# USB_Debug.net
KiCad netlist of a schematic drawn in Altium Designer
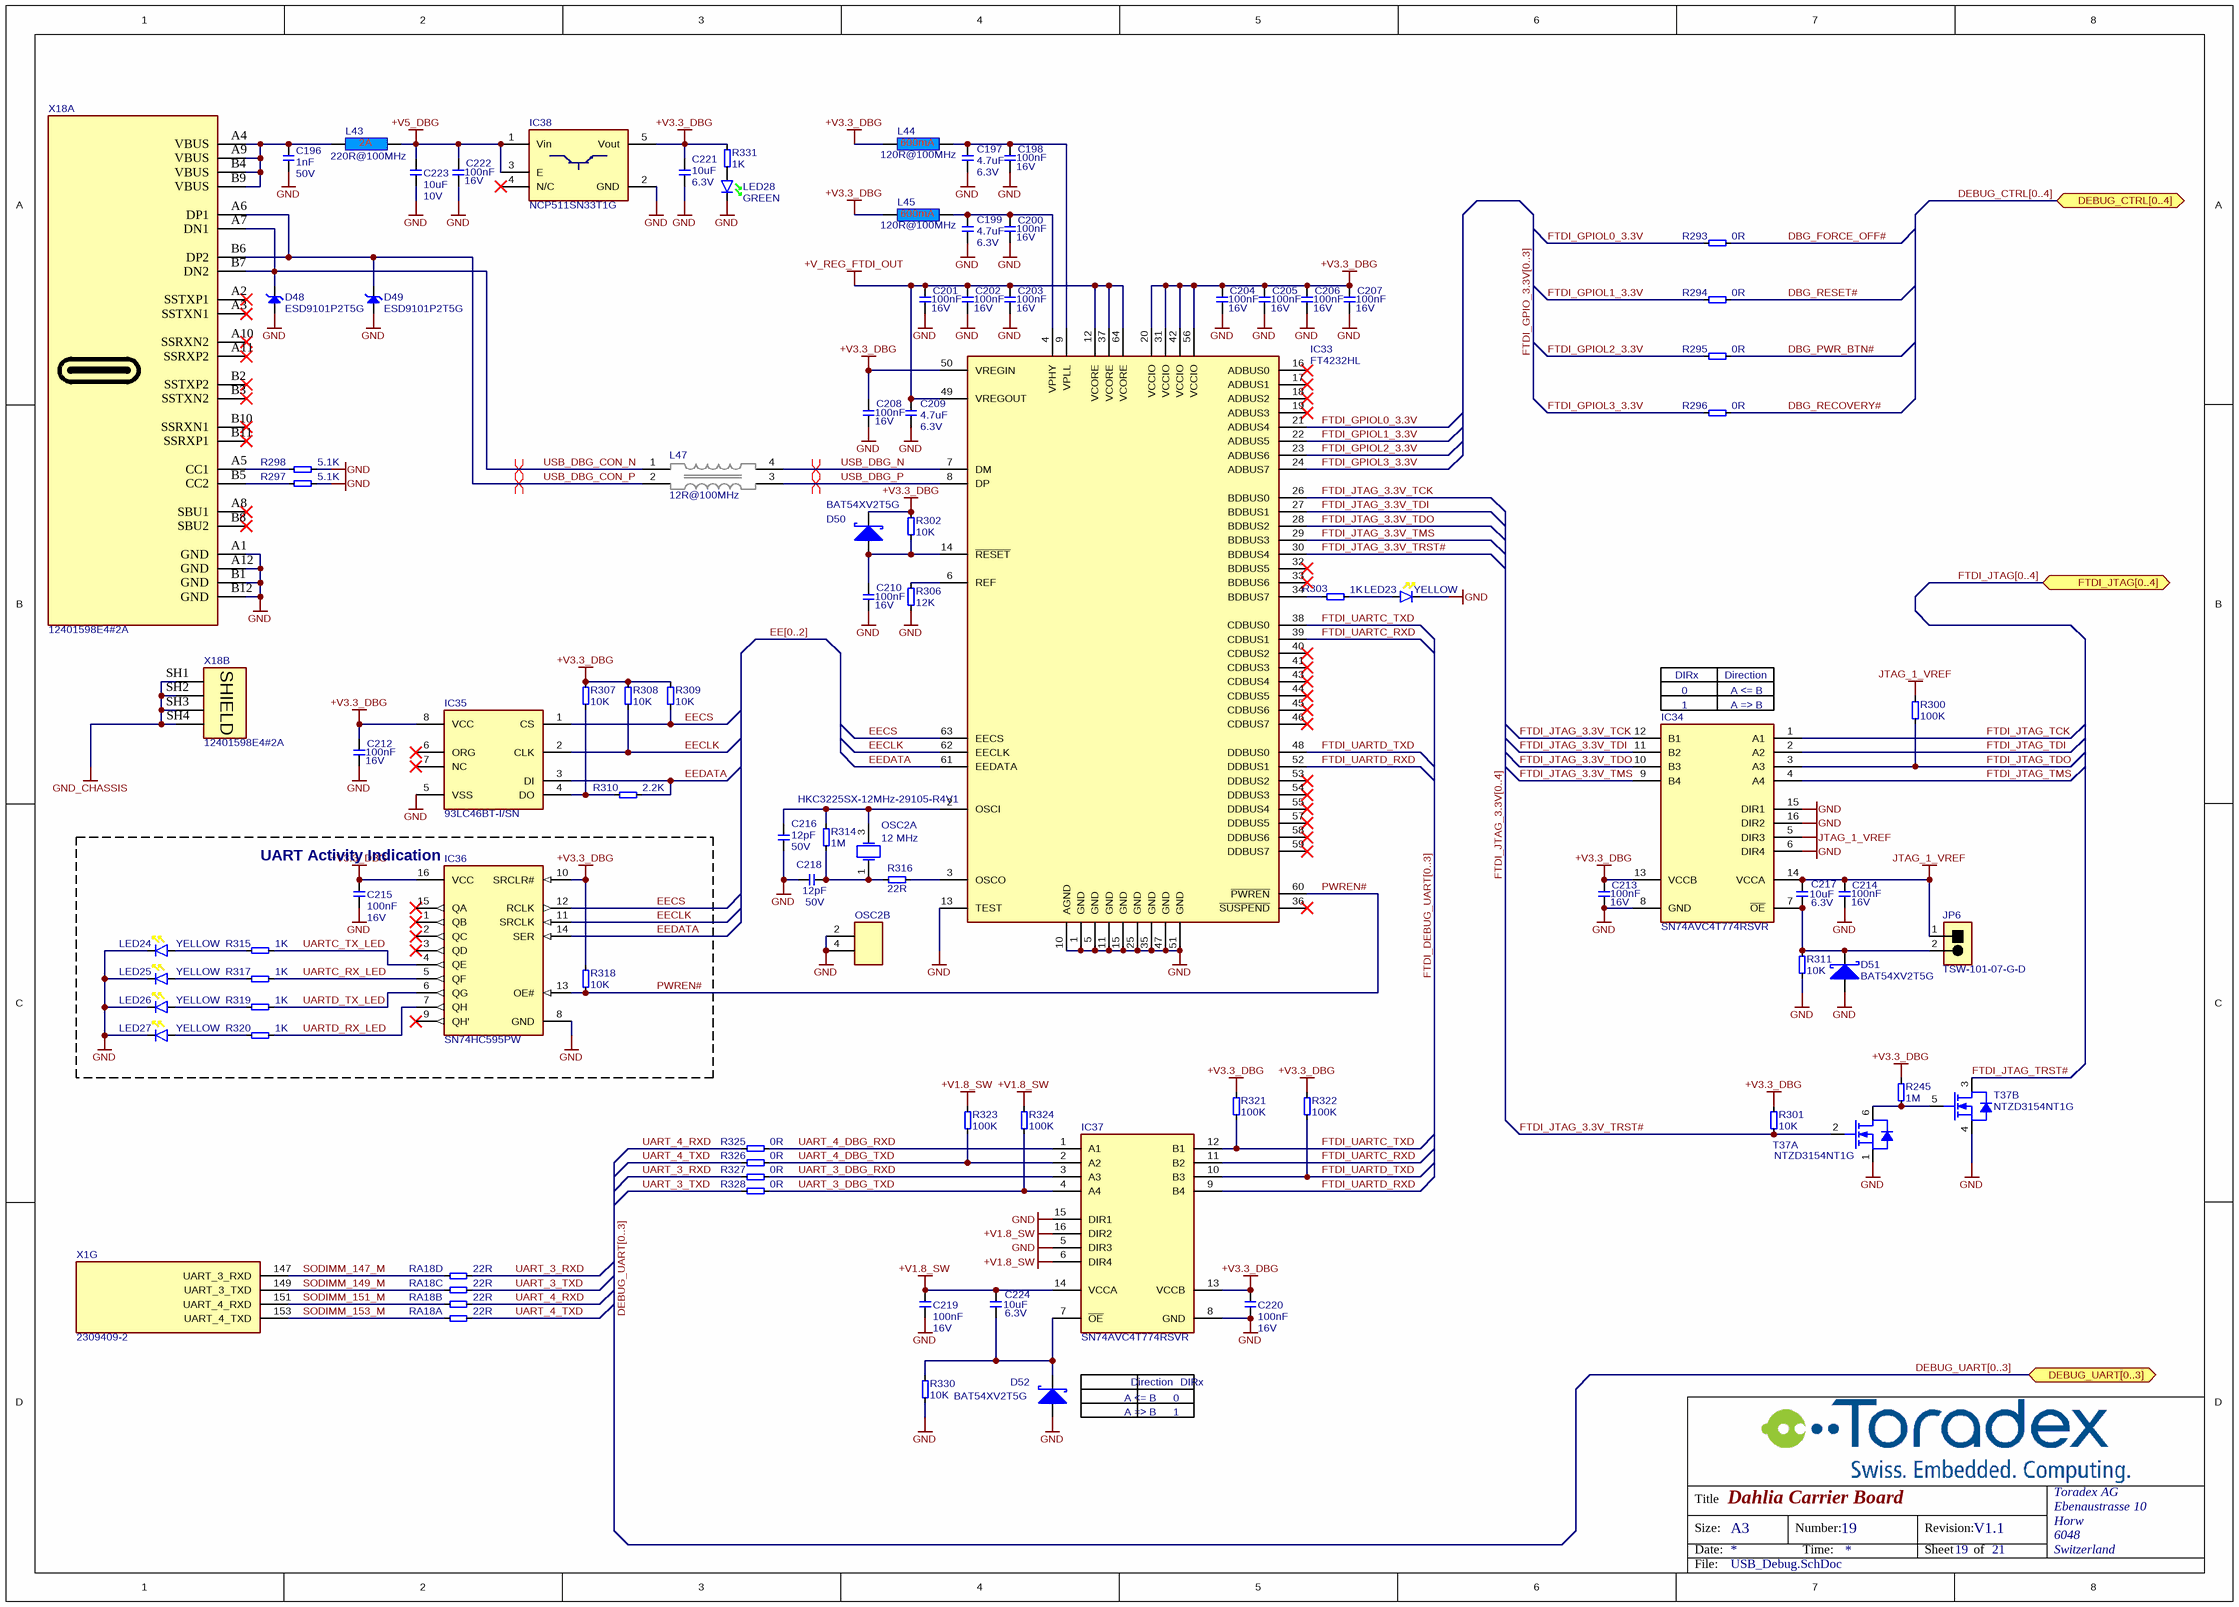
[diagram p0: USB_Debug.SchDoc]

(export (version "E")
  (design (tool "Eeschema 10.0.6"))
  (components
    (comp (ref "C196")
      (value "1nF")
      (footprint "CAPC1005X60N")
      (description "Capacitor Ceramic X7R 1nF 50V 10% 0402")
      (fields (field (name "TOLERANCE") "10%") (field (name "RATING") "50V"))
      (libsource (lib "Dahlia Carrier Board") (part "C-X7R-1nF-50V-10%-0402"))
    )
    (comp (ref "C197")
      (value "4.7uF")
      (footprint "CAPC1005X60N")
      (description "Capacitor Ceramic X5R 4.7uF 6.3V 20% 0402")
      (fields (field (name "TOLERANCE") "20%") (field (name "RATING") "6.3V"))
      (libsource (lib "Dahlia Carrier Board") (part "C-X5R-4.7u-6.3V-20%-0402"))
    )
    (comp (ref "C198")
      (value "100nF")
      (footprint "CAPC1005X60N")
      (description "Capacitor Ceramic X7R 100nF 16V 10% 0402")
      (fields (field (name "TOLERANCE") "10%") (field (name "RATING") "16V"))
      (libsource (lib "Dahlia Carrier Board") (part "C-X7R-100nF-16V-10%-0402"))
    )
    (comp (ref "C199")
      (value "4.7uF")
      (footprint "CAPC1005X60N")
      (description "Capacitor Ceramic X5R 4.7uF 6.3V 20% 0402")
      (fields (field (name "TOLERANCE") "20%") (field (name "RATING") "6.3V"))
      (libsource (lib "Dahlia Carrier Board") (part "C-X5R-4.7u-6.3V-20%-0402"))
    )
    (comp (ref "C200")
      (value "100nF")
      (footprint "CAPC1005X60N")
      (description "Capacitor Ceramic X7R 100nF 16V 10% 0402")
      (fields (field (name "TOLERANCE") "10%") (field (name "RATING") "16V"))
      (libsource (lib "Dahlia Carrier Board") (part "C-X7R-100nF-16V-10%-0402"))
    )
    (comp (ref "C201")
      (value "100nF")
      (footprint "CAPC1005X60N")
      (description "Capacitor Ceramic X7R 100nF 16V 10% 0402")
      (fields (field (name "TOLERANCE") "10%") (field (name "RATING") "16V"))
      (libsource (lib "Dahlia Carrier Board") (part "C-X7R-100nF-16V-10%-0402"))
    )
    (comp (ref "C202")
      (value "100nF")
      (footprint "CAPC1005X60N")
      (description "Capacitor Ceramic X7R 100nF 16V 10% 0402")
      (fields (field (name "TOLERANCE") "10%") (field (name "RATING") "16V"))
      (libsource (lib "Dahlia Carrier Board") (part "C-X7R-100nF-16V-10%-0402"))
    )
    (comp (ref "C203")
      (value "100nF")
      (footprint "CAPC1005X60N")
      (description "Capacitor Ceramic X7R 100nF 16V 10% 0402")
      (fields (field (name "TOLERANCE") "10%") (field (name "RATING") "16V"))
      (libsource (lib "Dahlia Carrier Board") (part "C-X7R-100nF-16V-10%-0402"))
    )
    (comp (ref "C204")
      (value "100nF")
      (footprint "CAPC1005X60N")
      (description "Capacitor Ceramic X7R 100nF 16V 10% 0402")
      (fields (field (name "TOLERANCE") "10%") (field (name "RATING") "16V"))
      (libsource (lib "Dahlia Carrier Board") (part "C-X7R-100nF-16V-10%-0402"))
    )
    (comp (ref "C205")
      (value "100nF")
      (footprint "CAPC1005X60N")
      (description "Capacitor Ceramic X7R 100nF 16V 10% 0402")
      (fields (field (name "TOLERANCE") "10%") (field (name "RATING") "16V"))
      (libsource (lib "Dahlia Carrier Board") (part "C-X7R-100nF-16V-10%-0402"))
    )
    (comp (ref "C206")
      (value "100nF")
      (footprint "CAPC1005X60N")
      (description "Capacitor Ceramic X7R 100nF 16V 10% 0402")
      (fields (field (name "TOLERANCE") "10%") (field (name "RATING") "16V"))
      (libsource (lib "Dahlia Carrier Board") (part "C-X7R-100nF-16V-10%-0402"))
    )
    (comp (ref "C207")
      (value "100nF")
      (footprint "CAPC1005X60N")
      (description "Capacitor Ceramic X7R 100nF 16V 10% 0402")
      (fields (field (name "TOLERANCE") "10%") (field (name "RATING") "16V"))
      (libsource (lib "Dahlia Carrier Board") (part "C-X7R-100nF-16V-10%-0402"))
    )
    (comp (ref "C208")
      (value "100nF")
      (footprint "CAPC1005X60N")
      (description "Capacitor Ceramic X7R 100nF 16V 10% 0402")
      (fields (field (name "TOLERANCE") "10%") (field (name "RATING") "16V"))
      (libsource (lib "Dahlia Carrier Board") (part "C-X7R-100nF-16V-10%-0402"))
    )
    (comp (ref "C209")
      (value "4.7uF")
      (footprint "CAPC1005X60N")
      (description "Capacitor Ceramic X5R 4.7uF 6.3V 20% 0402")
      (fields (field (name "TOLERANCE") "20%") (field (name "RATING") "6.3V"))
      (libsource (lib "Dahlia Carrier Board") (part "C-X5R-4.7u-6.3V-20%-0402"))
    )
    (comp (ref "C210")
      (value "100nF")
      (footprint "CAPC1005X60N")
      (description "Capacitor Ceramic X7R 100nF 16V 10% 0402")
      (fields (field (name "TOLERANCE") "10%") (field (name "RATING") "16V"))
      (libsource (lib "Dahlia Carrier Board") (part "C-X7R-100nF-16V-10%-0402"))
    )
    (comp (ref "C212")
      (value "100nF")
      (footprint "CAPC1005X60N")
      (description "Capacitor Ceramic X7R 100nF 16V 10% 0402")
      (fields (field (name "TOLERANCE") "10%") (field (name "RATING") "16V"))
      (libsource (lib "Dahlia Carrier Board") (part "C-X7R-100nF-16V-10%-0402"))
    )
    (comp (ref "C213")
      (value "100nF")
      (footprint "CAPC1005X60N")
      (description "Capacitor Ceramic X7R 100nF 16V 10% 0402")
      (fields (field (name "TOLERANCE") "10%") (field (name "RATING") "16V"))
      (libsource (lib "Dahlia Carrier Board") (part "C-X7R-100nF-16V-10%-0402"))
    )
    (comp (ref "C214")
      (value "100nF")
      (footprint "CAPC1005X60N")
      (description "Capacitor Ceramic X7R 100nF 16V 10% 0402")
      (fields (field (name "TOLERANCE") "10%") (field (name "RATING") "16V"))
      (libsource (lib "Dahlia Carrier Board") (part "C-X7R-100nF-16V-10%-0402"))
    )
    (comp (ref "C215")
      (value "100nF")
      (footprint "CAPC1005X60N")
      (description "Capacitor Ceramic X7R 100nF 16V 10% 0402")
      (fields (field (name "TOLERANCE") "10%") (field (name "RATING") "16V"))
      (libsource (lib "Dahlia Carrier Board") (part "C-X7R-100nF-16V-10%-0402"))
    )
    (comp (ref "C216")
      (value "12pF")
      (footprint "CAPC1005X60N")
      (description "Capacitor Ceramic NP0  12pF 50V 5% 0402")
      (fields (field (name "TOLERANCE") "5%") (field (name "RATING") "50V"))
      (libsource (lib "Dahlia Carrier Board") (part "C-NP0-12p-50V-5%-0402"))
    )
    (comp (ref "C217")
      (value "10uF")
      (footprint "CAPC1005X60N")
      (description "Capacitor Ceramic X5R 10uF 6.3V 20% 0402")
      (fields (field (name "TOLERANCE") "20%") (field (name "RATING") "6.3V"))
      (libsource (lib "Dahlia Carrier Board") (part "C-X5R-10u-6.3V-20%-0402"))
    )
    (comp (ref "C218")
      (value "12pF")
      (footprint "CAPC1005X60N")
      (description "Capacitor Ceramic NP0  12pF 50V 5% 0402")
      (fields (field (name "TOLERANCE") "5%") (field (name "RATING") "50V"))
      (libsource (lib "Dahlia Carrier Board") (part "C-NP0-12p-50V-5%-0402"))
    )
    (comp (ref "C219")
      (value "100nF")
      (footprint "CAPC1005X60N")
      (description "Capacitor Ceramic X7R 100nF 16V 10% 0402")
      (fields (field (name "TOLERANCE") "10%") (field (name "RATING") "16V"))
      (libsource (lib "Dahlia Carrier Board") (part "C-X7R-100nF-16V-10%-0402"))
    )
    (comp (ref "C220")
      (value "100nF")
      (footprint "CAPC1005X60N")
      (description "Capacitor Ceramic X7R 100nF 16V 10% 0402")
      (fields (field (name "TOLERANCE") "10%") (field (name "RATING") "16V"))
      (libsource (lib "Dahlia Carrier Board") (part "C-X7R-100nF-16V-10%-0402"))
    )
    (comp (ref "C221")
      (value "10uF")
      (footprint "CAPC1005X60N")
      (description "Capacitor Ceramic X5R 10uF 6.3V 20% 0402")
      (fields (field (name "TOLERANCE") "20%") (field (name "RATING") "6.3V"))
      (libsource (lib "Dahlia Carrier Board") (part "C-X5R-10u-6.3V-20%-0402"))
    )
    (comp (ref "C222")
      (value "100nF")
      (footprint "CAPC1005X60N")
      (description "Capacitor Ceramic X7R 100nF 16V 10% 0402")
      (fields (field (name "TOLERANCE") "10%") (field (name "RATING") "16V"))
      (libsource (lib "Dahlia Carrier Board") (part "C-X7R-100nF-16V-10%-0402"))
    )
    (comp (ref "C223")
      (value "10uF")
      (footprint "T_CAPC0603X33N")
      (description "Capacitor Ceramic X5R 10uF 10V 20% 0603")
      (fields (field (name "TOLERANCE") "20%") (field (name "RATING") "10V"))
      (libsource (lib "Dahlia Carrier Board") (part "C-X5R-10uF-10V-20%-0603"))
    )
    (comp (ref "C224")
      (value "10uF")
      (footprint "CAPC1005X60N")
      (description "Capacitor Ceramic X5R 10uF 6.3V 20% 0402")
      (fields (field (name "TOLERANCE") "20%") (field (name "RATING") "6.3V"))
      (libsource (lib "Dahlia Carrier Board") (part "C-X5R-10u-6.3V-20%-0402"))
    )
    (comp (ref "D48")
      (value "ESD9101P2T5G")
      (footprint "SOD-923")
      (description "ESD Protection Diode")
      (fields (field (name "MANUFACTURER PART NO.") "ESD9101P2T5G"))
      (libsource (lib "Dahlia Carrier Board") (part "D-OnSemi-ESD9101P2T5G"))
    )
    (comp (ref "D49")
      (value "ESD9101P2T5G")
      (footprint "SOD-923")
      (description "ESD Protection Diode")
      (fields (field (name "MANUFACTURER PART NO.") "ESD9101P2T5G"))
      (libsource (lib "Dahlia Carrier Board") (part "D-OnSemi-ESD9101P2T5G"))
    )
    (comp (ref "D50")
      (value "BAT54XV2T5G")
      (footprint "SOD-523")
      (description "Schottky Barrier Rectifier")
      (fields (field (name "MANUFACTURER PART NO.") "BAT54XV2T5G"))
      (libsource (lib "Dahlia Carrier Board") (part "D-BAT54-SOD523"))
    )
    (comp (ref "D51")
      (value "BAT54XV2T5G")
      (footprint "SOD-523")
      (description "Schottky Barrier Rectifier")
      (fields (field (name "MANUFACTURER PART NO.") "BAT54XV2T5G"))
      (libsource (lib "Dahlia Carrier Board") (part "D-BAT54-SOD523"))
    )
    (comp (ref "D52")
      (value "BAT54XV2T5G")
      (footprint "SOD-523")
      (description "Schottky Barrier Rectifier")
      (fields (field (name "MANUFACTURER PART NO.") "BAT54XV2T5G"))
      (libsource (lib "Dahlia Carrier Board") (part "D-BAT54-SOD523"))
    )
    (comp (ref "IC33")
      (value "FT4232HL")
      (footprint "LQFP-64")
      (description "Quad High Speed USB to Multipurpose UART/MPSSE")
      (fields (field (name "MANUFACTURER PART NO.") "FT4232HL"))
      (libsource (lib "Dahlia Carrier Board") (part "IC-FTDI-FT4232HL"))
    )
    (comp (ref "IC34")
      (value "SN74AVC4T774RSVR")
      (footprint "IC-UQFN40P180X210X55-16N")
      (description "4 Bit Bidirectional l Voltage Level Translator, Configurable Direction, UFQFN-16 package")
      (fields (field (name "MANUFACTURER PART NO.") "SN74AVC4T774RSVR"))
      (libsource (lib "") (part "IC-TI-SN74AVC4T774RSVR_1"))
    )
    (comp (ref "IC35")
      (value "93LC46BT")
      (footprint "SOIC127P600X173-8N")
      (description "EEPROM, 1k, 64x16, serial, SOIC8")
      (fields (field (name "MANUFACTURER PART NO.") "93LC46BT-I/SN"))
      (libsource (lib "Dahlia Carrier Board") (part "IC-MC-93LC46BT-I/SN"))
    )
    (comp (ref "IC36")
      (value "SN74HC595PW")
      (footprint "IC_TSOP65P640X120-16N")
      (description "8-Bit Shift Registers With 3-State Output Registers")
      (fields (field (name "MANUFACTURER PART NO.") "SN74HC595PW"))
      (libsource (lib "Dahlia Carrier Board") (part "IC-TI-SN74HC595PW"))
    )
    (comp (ref "IC37")
      (value "SN74AVC4T774RSVR")
      (footprint "IC-UQFN40P180X210X55-16N")
      (description "4 Bit Bidirectional l Voltage Level Translator, Configurable Direction, UFQFN-16 package")
      (fields (field (name "MANUFACTURER PART NO.") "SN74AVC4T774RSVR"))
      (libsource (lib "Dahlia Carrier Board") (part "IC-TI-SN74AVC4T774RSVR"))
    )
    (comp (ref "IC38")
      (value "NCP511SN33T1G")
      (footprint "SOT95P279X142-5N")
      (description "NCP511SN33T1G LDO Regulator")
      (fields (field (name "MANUFACTURER PART NO.") "NCP511SN33T1G"))
      (libsource (lib "Dahlia Carrier Board") (part "IC-ON-NCP511SN33T1G"))
    )
    (comp (ref "JP6")
      (value "TSW-101-07-G-D")
      (footprint "T_Samtec_TSW-101-07-G-D")
      (description "Header male, 1x2 Pins, 2.54 mm pitch")
      (libsource (lib "Dahlia Carrier Board") (part "CON-Samtec-TSW-101-07-G-D"))
    )
    (comp (ref "L43")
      (value "220R@100MHz")
      (footprint "INDC1608X95N")
      (description "220R@100MHz 2A EMI FILTER")
      (fields (field (name "TOLERANCE") "25%"))
      (libsource (lib "Dahlia Carrier Board") (part "L-220R@100MHz-2A-25%-0603"))
    )
    (comp (ref "L44")
      (value "120R@100MHz")
      (footprint "INDC1005X60N")
      (description "120R@100MHz 600mA EMI FILTER")
      (fields (field (name "TOLERANCE") "25%"))
      (libsource (lib "Dahlia Carrier Board") (part "Lemv-120R-600mA-25%-0402"))
    )
    (comp (ref "L45")
      (value "120R@100MHz")
      (footprint "INDC1005X60N")
      (description "120R@100MHz 600mA EMI FILTER")
      (fields (field (name "TOLERANCE") "25%"))
      (libsource (lib "Dahlia Carrier Board") (part "Lemv-120R-600mA-25%-0402"))
    )
    (comp (ref "L47")
      (value "12R@100MHz")
      (footprint "T_Panasonic_EXC14CH120U")
      (description "Common Mode Choke High Speed 12R 100mA")
      (fields (field (name "TOLERANCE") "25%") (field (name "MANUFACTURER PART NO.") "EXC14CH120U"))
      (libsource (lib "Dahlia Carrier Board") (part "L-Panasonic-EXC14CH120U-12R@100MHz-1000mA-25%"))
    )
    (comp (ref "LED23")
      (value "LTST-C190KSKT")
      (footprint "T_Liteon_LTST-C190KSKT")
      (description "LED yellow Lite-On LTST-C190KSKT")
      (fields (field (name "COLOR") "YELLOW"))
      (libsource (lib "Dahlia Carrier Board") (part "LED-LiteOn-LTST-C190KSKT"))
    )
    (comp (ref "LED24")
      (value "LTST-C190KSKT")
      (footprint "T_Liteon_LTST-C190KSKT")
      (description "LED yellow Lite-On LTST-C190KSKT")
      (fields (field (name "COLOR") "YELLOW"))
      (libsource (lib "Dahlia Carrier Board") (part "LED-LiteOn-LTST-C190KSKT"))
    )
    (comp (ref "LED25")
      (value "LTST-C190KSKT")
      (footprint "T_Liteon_LTST-C190KSKT")
      (description "LED yellow Lite-On LTST-C190KSKT")
      (fields (field (name "COLOR") "YELLOW"))
      (libsource (lib "Dahlia Carrier Board") (part "LED-LiteOn-LTST-C190KSKT"))
    )
    (comp (ref "LED26")
      (value "LTST-C190KSKT")
      (footprint "T_Liteon_LTST-C190KSKT")
      (description "LED yellow Lite-On LTST-C190KSKT")
      (fields (field (name "COLOR") "YELLOW"))
      (libsource (lib "Dahlia Carrier Board") (part "LED-LiteOn-LTST-C190KSKT"))
    )
    (comp (ref "LED27")
      (value "LTST-C190KSKT")
      (footprint "T_Liteon_LTST-C190KSKT")
      (description "LED yellow Lite-On LTST-C190KSKT")
      (fields (field (name "COLOR") "YELLOW"))
      (libsource (lib "Dahlia Carrier Board") (part "LED-LiteOn-LTST-C190KSKT"))
    )
    (comp (ref "LED28")
      (value "LTST-C190GKT")
      (footprint "T_Liteon_LTST-C190GKT")
      (description "LED green Lite-ON LTST-C190GKT")
      (fields (field (name "COLOR") "GREEN"))
      (libsource (lib "Dahlia Carrier Board") (part "LED-LiteOn-LTST-C190GKT"))
    )
    (comp (ref "OSC2")
      (value "HKC3225SX-12MHz-29105-R4V1")
      (footprint "OSC-SMD-3.2mmx2.5mm")
      (fields (field (name "TOLERANCE") "+/- 30 ppm") (field (name "ALTIUM_VALUE") "12 MHz"))
      (libsource (lib "Dahlia Carrier Board") (part "OSC-HKC-HKC3225SX-12MHz-29105-R4V1"))
    )
    (comp (ref "R245")
      (value "1M")
      (footprint "RESC1005X40N")
      (description "Resistor 1 Mohm 63mW 5% 0402")
      (fields (field (name "TOLERANCE") "5%"))
      (libsource (lib "Dahlia Carrier Board") (part "R-1M-63mW-5%-0402"))
    )
    (comp (ref "R293")
      (value "0R")
      (footprint "T_RESC0603X30N")
      (description "Resistor 0 ohm 63mW 1% 0603")
      (fields (field (name "TOLERANCE") "1%"))
      (libsource (lib "Dahlia Carrier Board") (part "R-0R-63mW-1%-0603"))
    )
    (comp (ref "R294")
      (value "0R")
      (footprint "T_RESC0603X30N")
      (description "Resistor 0 ohm 63mW 1% 0603")
      (fields (field (name "TOLERANCE") "1%"))
      (libsource (lib "Dahlia Carrier Board") (part "R-0R-63mW-1%-0603"))
    )
    (comp (ref "R295")
      (value "0R")
      (footprint "T_RESC0603X30N")
      (description "Resistor 0 ohm 63mW 1% 0603")
      (fields (field (name "TOLERANCE") "1%"))
      (libsource (lib "Dahlia Carrier Board") (part "R-0R-63mW-1%-0603"))
    )
    (comp (ref "R296")
      (value "0R")
      (footprint "T_RESC0603X30N")
      (description "Resistor 0 ohm 63mW 1% 0603")
      (fields (field (name "TOLERANCE") "1%"))
      (libsource (lib "Dahlia Carrier Board") (part "R-0R-63mW-1%-0603"))
    )
    (comp (ref "R297")
      (value "5.1K")
      (footprint "T_RESC0603X30N")
      (description "Resistor 5.1 Kohm 63mW 1% 0603")
      (fields (field (name "TOLERANCE") "1%"))
      (libsource (lib "Dahlia Carrier Board") (part "R-5.1K-63mW-1%-0603"))
    )
    (comp (ref "R298")
      (value "5.1K")
      (footprint "T_RESC0603X30N")
      (description "Resistor 5.1 Kohm 63mW 1% 0603")
      (fields (field (name "TOLERANCE") "1%"))
      (libsource (lib "Dahlia Carrier Board") (part "R-5.1K-63mW-1%-0603"))
    )
    (comp (ref "R300")
      (value "100K")
      (footprint "RESC1005X40N")
      (description "Resistor 100 Kohm 63mW 5% 0402")
      (fields (field (name "TOLERANCE") "5%"))
      (libsource (lib "Dahlia Carrier Board") (part "R-100K-63mW-5%-0402"))
    )
    (comp (ref "R301")
      (value "10K")
      (footprint "RESC1005X40N")
      (description "Resistor 10 Kohm 63mW 5% 0402")
      (fields (field (name "TOLERANCE") "5%"))
      (libsource (lib "Dahlia Carrier Board") (part "R-10K-63mW-5%-0402"))
    )
    (comp (ref "R302")
      (value "10K")
      (footprint "RESC1005X40N")
      (description "Resistor 10 Kohm 63mW 5% 0402")
      (fields (field (name "TOLERANCE") "5%"))
      (libsource (lib "Dahlia Carrier Board") (part "R-10K-63mW-5%-0402"))
    )
    (comp (ref "R303")
      (value "1K")
      (footprint "RESC1005X40N")
      (description "Resistor 1 Kohm 63mW 5% 0402")
      (fields (field (name "TOLERANCE") "5%"))
      (libsource (lib "Dahlia Carrier Board") (part "R-1K-63mW-5%-0402"))
    )
    (comp (ref "R306")
      (value "12K")
      (footprint "RESC1005X40N")
      (description "Resistor 12 Kohm 63mW 1% 0402")
      (fields (field (name "TOLERANCE") "1%"))
      (libsource (lib "Dahlia Carrier Board") (part "R-12K-63mW-1%-0402"))
    )
    (comp (ref "R307")
      (value "10K")
      (footprint "RESC1005X40N")
      (description "Resistor 10 Kohm 63mW 5% 0402")
      (fields (field (name "TOLERANCE") "5%"))
      (libsource (lib "Dahlia Carrier Board") (part "R-10K-63mW-5%-0402"))
    )
    (comp (ref "R308")
      (value "10K")
      (footprint "RESC1005X40N")
      (description "Resistor 10 Kohm 63mW 5% 0402")
      (fields (field (name "TOLERANCE") "5%"))
      (libsource (lib "Dahlia Carrier Board") (part "R-10K-63mW-5%-0402"))
    )
    (comp (ref "R309")
      (value "10K")
      (footprint "RESC1005X40N")
      (description "Resistor 10 Kohm 63mW 5% 0402")
      (fields (field (name "TOLERANCE") "5%"))
      (libsource (lib "Dahlia Carrier Board") (part "R-10K-63mW-5%-0402"))
    )
    (comp (ref "R310")
      (value "2.2K")
      (footprint "RESC1005X40N")
      (description "Resistor 2.2 Kohm 63mW 5% 0402")
      (fields (field (name "TOLERANCE") "5%"))
      (libsource (lib "Dahlia Carrier Board") (part "R-2.2K-63mW-5%-0402"))
    )
    (comp (ref "R311")
      (value "10K")
      (footprint "RESC1005X40N")
      (description "Resistor 10 Kohm 63mW 5% 0402")
      (fields (field (name "TOLERANCE") "5%"))
      (libsource (lib "Dahlia Carrier Board") (part "R-10K-63mW-5%-0402"))
    )
    (comp (ref "R314")
      (value "1M")
      (footprint "T_RESC0603X30N")
      (description "Resistor 1Mohm 63mW 5% 0603")
      (fields (field (name "TOLERANCE") "5%") (field (name "Comment") "1MR"))
      (libsource (lib "Dahlia Carrier Board") (part "R-1M-63mW-5%-0603"))
    )
    (comp (ref "R315")
      (value "1K")
      (footprint "RESC1005X40N")
      (description "Resistor 1 Kohm 63mW 5% 0402")
      (fields (field (name "TOLERANCE") "5%"))
      (libsource (lib "Dahlia Carrier Board") (part "R-1K-63mW-5%-0402"))
    )
    (comp (ref "R316")
      (value "22R")
      (footprint "RESC1005X40N")
      (description "Resistor 22 ohm 63mW 5% 0402")
      (fields (field (name "TOLERANCE") "5%"))
      (libsource (lib "Dahlia Carrier Board") (part "R-22R-63mW-5%-0402"))
    )
    (comp (ref "R317")
      (value "1K")
      (footprint "RESC1005X40N")
      (description "Resistor 1 Kohm 63mW 5% 0402")
      (fields (field (name "TOLERANCE") "5%"))
      (libsource (lib "Dahlia Carrier Board") (part "R-1K-63mW-5%-0402"))
    )
    (comp (ref "R318")
      (value "10K")
      (footprint "RESC1005X40N")
      (description "Resistor 10 Kohm 63mW 5% 0402")
      (fields (field (name "TOLERANCE") "5%"))
      (libsource (lib "Dahlia Carrier Board") (part "R-10K-63mW-5%-0402"))
    )
    (comp (ref "R319")
      (value "1K")
      (footprint "RESC1005X40N")
      (description "Resistor 1 Kohm 63mW 5% 0402")
      (fields (field (name "TOLERANCE") "5%"))
      (libsource (lib "Dahlia Carrier Board") (part "R-1K-63mW-5%-0402"))
    )
    (comp (ref "R320")
      (value "1K")
      (footprint "RESC1005X40N")
      (description "Resistor 1 Kohm 63mW 5% 0402")
      (fields (field (name "TOLERANCE") "5%"))
      (libsource (lib "Dahlia Carrier Board") (part "R-1K-63mW-5%-0402"))
    )
    (comp (ref "R321")
      (value "100K")
      (footprint "RESC1005X40N")
      (description "Resistor 100 Kohm 63mW 5% 0402")
      (fields (field (name "TOLERANCE") "5%"))
      (libsource (lib "Dahlia Carrier Board") (part "R-100K-63mW-5%-0402"))
    )
    (comp (ref "R322")
      (value "100K")
      (footprint "RESC1005X40N")
      (description "Resistor 100 Kohm 63mW 5% 0402")
      (fields (field (name "TOLERANCE") "5%"))
      (libsource (lib "Dahlia Carrier Board") (part "R-100K-63mW-5%-0402"))
    )
    (comp (ref "R323")
      (value "100K")
      (footprint "RESC1005X40N")
      (description "Resistor 100 Kohm 63mW 5% 0402")
      (fields (field (name "TOLERANCE") "5%"))
      (libsource (lib "Dahlia Carrier Board") (part "R-100K-63mW-5%-0402"))
    )
    (comp (ref "R324")
      (value "100K")
      (footprint "RESC1005X40N")
      (description "Resistor 100 Kohm 63mW 5% 0402")
      (fields (field (name "TOLERANCE") "5%"))
      (libsource (lib "Dahlia Carrier Board") (part "R-100K-63mW-5%-0402"))
    )
    (comp (ref "R325")
      (value "0R")
      (footprint "T_RESC0603X30N")
      (description "Resistor 0 ohm 63mW 1% 0603")
      (fields (field (name "TOLERANCE") "1%"))
      (libsource (lib "Dahlia Carrier Board") (part "R-0R-63mW-1%-0603"))
    )
    (comp (ref "R326")
      (value "0R")
      (footprint "T_RESC0603X30N")
      (description "Resistor 0 ohm 63mW 1% 0603")
      (fields (field (name "TOLERANCE") "1%"))
      (libsource (lib "Dahlia Carrier Board") (part "R-0R-63mW-1%-0603"))
    )
    (comp (ref "R327")
      (value "0R")
      (footprint "T_RESC0603X30N")
      (description "Resistor 0 ohm 63mW 1% 0603")
      (fields (field (name "TOLERANCE") "1%"))
      (libsource (lib "Dahlia Carrier Board") (part "R-0R-63mW-1%-0603"))
    )
    (comp (ref "R328")
      (value "0R")
      (footprint "T_RESC0603X30N")
      (description "Resistor 0 ohm 63mW 1% 0603")
      (fields (field (name "TOLERANCE") "1%"))
      (libsource (lib "Dahlia Carrier Board") (part "R-0R-63mW-1%-0603"))
    )
    (comp (ref "R330")
      (value "10K")
      (footprint "RESC1005X40N")
      (description "Resistor 10 Kohm 63mW 5% 0402")
      (fields (field (name "TOLERANCE") "5%"))
      (libsource (lib "Dahlia Carrier Board") (part "R-10K-63mW-5%-0402"))
    )
    (comp (ref "R331")
      (value "1K")
      (footprint "RESC1005X40N")
      (description "Resistor 1 Kohm 63mW 5% 0402")
      (fields (field (name "TOLERANCE") "5%"))
      (libsource (lib "Dahlia Carrier Board") (part "R-1K-63mW-5%-0402"))
    )
    (comp (ref "RA18")
      (value "22R")
      (footprint "T_Resistor_Array_X4")
      (description "Resistor Array 22 R 63mW 5% 1206")
      (fields (field (name "TOLERANCE") "5%"))
      (libsource (lib "Dahlia Carrier Board") (part "RA-22R-63mW-5%-1206-div"))
    )
    (comp (ref "T37")
      (value "T-ONSemi-NTZD3154NT1G")
      (footprint "SOTFL50P160X60-6N")
      (description "Dual N-Channel 20V (D-S)  MOSFET")
      (fields (field (name "MANUFACTURER PART NO.") "NTZD3154NT1G"))
      (libsource (lib "Dahlia Carrier Board") (part "T-ONSemi-NTZD3154NT1G"))
    )
    (comp (ref "X1")
      (value "2309409-2")
      (footprint "CON-TE-2309409-2-SOLDERABLE-STANDOFFS")
      (description "DDR4 SODIMM Socket, 260 pins, 5.2mm(H), 0.5mm Pitch")
      (libsource (lib "Dahlia Carrier Board") (part "CON-TE-2309409-2"))
    )
    (comp (ref "X18")
      (value "12401598E4#2A")
      (footprint "CON-AMPHENOL-12401598E4#2A")
      (description "USB 3.1 Gen 2, Input Output Connectors, USB type C, Receptacle, Top mount, dual-row SMT, 1.6mmPCB")
      (fields (field (name "MANUFACTURER PART NO.") "12401598E4#2A"))
      (libsource (lib "Dahlia Carrier Board") (part "CON-Amphenol-12401598E4#2A"))
    )
  )
  (nets
    (net (code "31") (name "+V1.8_SW") (class "Default")
      (node (ref "C219") (pin "2") (pinfunction "2_2") (pintype "passive"))
      (node (ref "C224") (pin "2") (pinfunction "2_2") (pintype "passive"))
      (node (ref "IC37") (pin "14") (pinfunction "VCCA_14") (pintype "power_in"))
      (node (ref "IC37") (pin "16") (pinfunction "DIR2_16") (pintype "passive"))
      (node (ref "IC37") (pin "6") (pinfunction "DIR4_6") (pintype "passive"))
      (node (ref "R323") (pin "1") (pinfunction "1_1") (pintype "passive"))
      (node (ref "R324") (pin "2") (pinfunction "2_2") (pintype "passive"))
    )
    (net (code "32") (name "+V3.3_DBG") (class "Default")
      (node (ref "C204") (pin "2") (pinfunction "2_2") (pintype "passive"))
      (node (ref "C205") (pin "2") (pinfunction "2_2") (pintype "passive"))
      (node (ref "C206") (pin "2") (pinfunction "2_2") (pintype "passive"))
      (node (ref "C207") (pin "2") (pinfunction "2_2") (pintype "passive"))
      (node (ref "C208") (pin "2") (pinfunction "2_2") (pintype "passive"))
      (node (ref "C212") (pin "2") (pinfunction "2_2") (pintype "passive"))
      (node (ref "C213") (pin "2") (pinfunction "2_2") (pintype "passive"))
      (node (ref "C215") (pin "2") (pinfunction "2_2") (pintype "passive"))
      (node (ref "C220") (pin "2") (pinfunction "2_2") (pintype "passive"))
      (node (ref "C221") (pin "2") (pinfunction "2_2") (pintype "passive"))
      (node (ref "D50") (pin "C") (pinfunction "C_C") (pintype "passive"))
      (node (ref "IC33") (pin "20") (pinfunction "VCCIO_20") (pintype "passive"))
      (node (ref "IC33") (pin "31") (pinfunction "VCCIO_31") (pintype "passive"))
      (node (ref "IC33") (pin "42") (pinfunction "VCCIO_42") (pintype "passive"))
      (node (ref "IC33") (pin "50") (pinfunction "VREGIN_50") (pintype "passive"))
      (node (ref "IC33") (pin "56") (pinfunction "VCCIO_56") (pintype "passive"))
      (node (ref "IC34") (pin "13") (pinfunction "VCCB_13") (pintype "power_in"))
      (node (ref "IC35") (pin "8") (pinfunction "VCC_8") (pintype "passive"))
      (node (ref "IC36") (pin "10") (pinfunction "SRCLR#_10") (pintype "input"))
      (node (ref "IC36") (pin "16") (pinfunction "VCC_16") (pintype "power_in"))
      (node (ref "IC37") (pin "13") (pinfunction "VCCB_13") (pintype "power_in"))
      (node (ref "IC38") (pin "5") (pinfunction "Vout_5") (pintype "passive"))
      (node (ref "L44") (pin "1") (pinfunction "1_1") (pintype "passive"))
      (node (ref "L45") (pin "1") (pinfunction "1_1") (pintype "passive"))
      (node (ref "R245") (pin "2") (pinfunction "2_2") (pintype "passive"))
      (node (ref "R301") (pin "2") (pinfunction "2_2") (pintype "passive"))
      (node (ref "R302") (pin "2") (pinfunction "2_2") (pintype "passive"))
      (node (ref "R307") (pin "2") (pinfunction "2_2") (pintype "passive"))
      (node (ref "R308") (pin "2") (pinfunction "2_2") (pintype "passive"))
      (node (ref "R309") (pin "2") (pinfunction "2_2") (pintype "passive"))
      (node (ref "R318") (pin "2") (pinfunction "2_2") (pintype "passive"))
      (node (ref "R321") (pin "1") (pinfunction "1_1") (pintype "passive"))
      (node (ref "R322") (pin "2") (pinfunction "2_2") (pintype "passive"))
      (node (ref "R331") (pin "2") (pinfunction "2_2") (pintype "passive"))
    )
    (net (code "33") (name "+V5_DBG") (class "Default")
      (node (ref "C222") (pin "2") (pinfunction "2_2") (pintype "passive"))
      (node (ref "C223") (pin "2") (pinfunction "2_2") (pintype "passive"))
      (node (ref "IC38") (pin "1") (pinfunction "Vin_1") (pintype "passive"))
      (node (ref "IC38") (pin "3") (pinfunction "E_3") (pintype "passive"))
      (node (ref "L43") (pin "1") (pinfunction "1_1") (pintype "passive"))
    )
    (net (code "34") (name "+V_REG_FTDI_OUT") (class "Default")
      (node (ref "C201") (pin "2") (pinfunction "2_2") (pintype "passive"))
      (node (ref "C202") (pin "2") (pinfunction "2_2") (pintype "passive"))
      (node (ref "C203") (pin "2") (pinfunction "2_2") (pintype "passive"))
      (node (ref "C209") (pin "2") (pinfunction "2_2") (pintype "passive"))
      (node (ref "IC33") (pin "12") (pinfunction "VCORE_12") (pintype "passive"))
      (node (ref "IC33") (pin "37") (pinfunction "VCORE_37") (pintype "passive"))
      (node (ref "IC33") (pin "49") (pinfunction "VREGOUT_49") (pintype "passive"))
      (node (ref "IC33") (pin "64") (pinfunction "VCORE_64") (pintype "passive"))
    )
    (net (code "35") (name "/DBG_FORCE_OFF#") (class "Default")
      (node (ref "R293") (pin "2") (pinfunction "2_2") (pintype "passive"))
    )
    (net (code "36") (name "/DBG_PWR_BTN#") (class "Default")
      (node (ref "R295") (pin "2") (pinfunction "2_2") (pintype "passive"))
    )
    (net (code "37") (name "/DBG_RECOVERY#") (class "Default")
      (node (ref "R296") (pin "2") (pinfunction "2_2") (pintype "passive"))
    )
    (net (code "38") (name "/DBG_RESET#") (class "Default")
      (node (ref "R294") (pin "2") (pinfunction "2_2") (pintype "passive"))
    )
    (net (code "41") (name "/EECLK") (class "Default")
      (node (ref "IC33") (pin "62") (pinfunction "EECLK_62") (pintype "passive"))
      (node (ref "IC35") (pin "2") (pinfunction "CLK_2") (pintype "passive"))
      (node (ref "IC36") (pin "11") (pinfunction "SRCLK_11") (pintype "input"))
      (node (ref "R308") (pin "1") (pinfunction "1_1") (pintype "passive"))
    )
    (net (code "42") (name "/EECS") (class "Default")
      (node (ref "IC33") (pin "63") (pinfunction "EECS_63") (pintype "passive"))
      (node (ref "IC35") (pin "1") (pinfunction "CS_1") (pintype "passive"))
      (node (ref "IC36") (pin "12") (pinfunction "RCLK_12") (pintype "output"))
      (node (ref "R309") (pin "1") (pinfunction "1_1") (pintype "passive"))
    )
    (net (code "43") (name "/EEDATA") (class "Default")
      (node (ref "IC33") (pin "61") (pinfunction "EEDATA_61") (pintype "passive"))
      (node (ref "IC35") (pin "3") (pinfunction "DI_3") (pintype "passive"))
      (node (ref "IC36") (pin "14") (pinfunction "SER_14") (pintype "input"))
      (node (ref "R310") (pin "2") (pinfunction "2_2") (pintype "passive"))
    )
    (net (code "46") (name "/FTDI_GPIOL0_3.3V") (class "Default")
      (node (ref "IC33") (pin "21") (pinfunction "ADBUS4_21") (pintype "passive"))
      (node (ref "R293") (pin "1") (pinfunction "1_1") (pintype "passive"))
    )
    (net (code "47") (name "/FTDI_GPIOL1_3.3V") (class "Default")
      (node (ref "IC33") (pin "22") (pinfunction "ADBUS5_22") (pintype "passive"))
      (node (ref "R294") (pin "1") (pinfunction "1_1") (pintype "passive"))
    )
    (net (code "48") (name "/FTDI_GPIOL2_3.3V") (class "Default")
      (node (ref "IC33") (pin "23") (pinfunction "ADBUS6_23") (pintype "passive"))
      (node (ref "R295") (pin "1") (pinfunction "1_1") (pintype "passive"))
    )
    (net (code "49") (name "/FTDI_GPIOL3_3.3V") (class "Default")
      (node (ref "IC33") (pin "24") (pinfunction "ADBUS7_24") (pintype "passive"))
      (node (ref "R296") (pin "1") (pinfunction "1_1") (pintype "passive"))
    )
    (net (code "53") (name "/FTDI_JTAG_3.3V_TCK") (class "Default")
      (node (ref "IC33") (pin "26") (pinfunction "BDBUS0_26") (pintype "passive"))
      (node (ref "IC34") (pin "12") (pinfunction "B1_12") (pintype "passive"))
    )
    (net (code "54") (name "/FTDI_JTAG_3.3V_TDI") (class "Default")
      (node (ref "IC33") (pin "27") (pinfunction "BDBUS1_27") (pintype "passive"))
      (node (ref "IC34") (pin "11") (pinfunction "B2_11") (pintype "passive"))
    )
    (net (code "55") (name "/FTDI_JTAG_3.3V_TDO") (class "Default")
      (node (ref "IC33") (pin "28") (pinfunction "BDBUS2_28") (pintype "passive"))
      (node (ref "IC34") (pin "10") (pinfunction "B3_10") (pintype "passive"))
    )
    (net (code "56") (name "/FTDI_JTAG_3.3V_TMS") (class "Default")
      (node (ref "IC33") (pin "29") (pinfunction "BDBUS3_29") (pintype "passive"))
      (node (ref "IC34") (pin "9") (pinfunction "B4_9") (pintype "passive"))
    )
    (net (code "57") (name "/FTDI_JTAG_3.3V_TRST#") (class "Default")
      (node (ref "IC33") (pin "30") (pinfunction "BDBUS4_30") (pintype "passive"))
      (node (ref "R301") (pin "1") (pinfunction "1_1") (pintype "passive"))
      (node (ref "T37") (pin "2") (pinfunction "G_2") (pintype "passive"))
    )
    (net (code "58") (name "/FTDI_JTAG_TCK") (class "Default")
      (node (ref "IC34") (pin "1") (pinfunction "A1_1") (pintype "passive"))
    )
    (net (code "59") (name "/FTDI_JTAG_TDI") (class "Default")
      (node (ref "IC34") (pin "2") (pinfunction "A2_2") (pintype "passive"))
    )
    (net (code "60") (name "/FTDI_JTAG_TDO") (class "Default")
      (node (ref "IC34") (pin "3") (pinfunction "A3_3") (pintype "passive"))
      (node (ref "R300") (pin "1") (pinfunction "1_1") (pintype "passive"))
    )
    (net (code "61") (name "/FTDI_JTAG_TMS") (class "Default")
      (node (ref "IC34") (pin "4") (pinfunction "A4_4") (pintype "passive"))
    )
    (net (code "62") (name "/FTDI_JTAG_TRST#") (class "Default")
      (node (ref "T37") (pin "3") (pinfunction "D_3") (pintype "passive"))
    )
    (net (code "63") (name "/FTDI_UARTC_RXD") (class "Default")
      (node (ref "IC33") (pin "39") (pinfunction "CDBUS1_39") (pintype "passive"))
      (node (ref "IC37") (pin "11") (pinfunction "B2_11") (pintype "passive"))
    )
    (net (code "64") (name "/FTDI_UARTC_TXD") (class "Default")
      (node (ref "IC33") (pin "38") (pinfunction "CDBUS0_38") (pintype "passive"))
      (node (ref "IC37") (pin "12") (pinfunction "B1_12") (pintype "passive"))
      (node (ref "R321") (pin "2") (pinfunction "2_2") (pintype "passive"))
    )
    (net (code "65") (name "/FTDI_UARTD_RXD") (class "Default")
      (node (ref "IC33") (pin "52") (pinfunction "DDBUS1_52") (pintype "passive"))
      (node (ref "IC37") (pin "9") (pinfunction "B4_9") (pintype "passive"))
    )
    (net (code "66") (name "/FTDI_UARTD_TXD") (class "Default")
      (node (ref "IC33") (pin "48") (pinfunction "DDBUS0_48") (pintype "passive"))
      (node (ref "IC37") (pin "10") (pinfunction "B3_10") (pintype "passive"))
      (node (ref "R322") (pin "1") (pinfunction "1_1") (pintype "passive"))
    )
    (net (code "67") (name "/PWREN#") (class "Default")
      (node (ref "IC33") (pin "60") (pinfunction "~{PWREN}_60") (pintype "passive"))
      (node (ref "IC36") (pin "13") (pinfunction "OE#_13") (pintype "input"))
      (node (ref "R318") (pin "1") (pinfunction "1_1") (pintype "passive"))
    )
    (net (code "68") (name "/SODIMM_147_M") (class "Default")
      (node (ref "RA18") (pin "4") (pinfunction "4_4") (pintype "passive"))
      (node (ref "X1") (pin "147") (pinfunction "UART_3_RXD_147") (pintype "passive"))
    )
    (net (code "69") (name "/SODIMM_149_M") (class "Default")
      (node (ref "RA18") (pin "3") (pinfunction "3_3") (pintype "passive"))
      (node (ref "X1") (pin "149") (pinfunction "UART_3_TXD_149") (pintype "passive"))
    )
    (net (code "70") (name "/SODIMM_151_M") (class "Default")
      (node (ref "RA18") (pin "2") (pinfunction "2_2") (pintype "passive"))
      (node (ref "X1") (pin "151") (pinfunction "UART_4_RXD_151") (pintype "passive"))
    )
    (net (code "71") (name "/SODIMM_153_M") (class "Default")
      (node (ref "RA18") (pin "1") (pinfunction "1_1") (pintype "passive"))
      (node (ref "X1") (pin "153") (pinfunction "UART_4_TXD_153") (pintype "passive"))
    )
    (net (code "72") (name "/UARTC_RX_LED") (class "Default")
      (node (ref "IC36") (pin "5") (pinfunction "QF_5") (pintype "output"))
      (node (ref "R317") (pin "2") (pinfunction "2_2") (pintype "passive"))
    )
    (net (code "73") (name "/UARTC_TX_LED") (class "Default")
      (node (ref "IC36") (pin "4") (pinfunction "QE_4") (pintype "output"))
      (node (ref "R315") (pin "2") (pinfunction "2_2") (pintype "passive"))
    )
    (net (code "74") (name "/UARTD_RX_LED") (class "Default")
      (node (ref "IC36") (pin "7") (pinfunction "QH_7") (pintype "output"))
      (node (ref "R320") (pin "2") (pinfunction "2_2") (pintype "passive"))
    )
    (net (code "75") (name "/UARTD_TX_LED") (class "Default")
      (node (ref "IC36") (pin "6") (pinfunction "QG_6") (pintype "output"))
      (node (ref "R319") (pin "2") (pinfunction "2_2") (pintype "passive"))
    )
    (net (code "76") (name "/UART_3_DBG_RXD") (class "Default")
      (node (ref "IC37") (pin "3") (pinfunction "A3_3") (pintype "passive"))
      (node (ref "R327") (pin "2") (pinfunction "2_2") (pintype "passive"))
    )
    (net (code "77") (name "/UART_3_DBG_TXD") (class "Default")
      (node (ref "IC37") (pin "4") (pinfunction "A4_4") (pintype "passive"))
      (node (ref "R324") (pin "1") (pinfunction "1_1") (pintype "passive"))
      (node (ref "R328") (pin "2") (pinfunction "2_2") (pintype "passive"))
    )
    (net (code "78") (name "/UART_3_RXD") (class "Default")
      (node (ref "R327") (pin "1") (pinfunction "1_1") (pintype "passive"))
      (node (ref "RA18") (pin "8") (pinfunction "8_8") (pintype "passive"))
    )
    (net (code "79") (name "/UART_3_TXD") (class "Default")
      (node (ref "R328") (pin "1") (pinfunction "1_1") (pintype "passive"))
      (node (ref "RA18") (pin "7") (pinfunction "7_7") (pintype "passive"))
    )
    (net (code "80") (name "/UART_4_DBG_RXD") (class "Default")
      (node (ref "IC37") (pin "1") (pinfunction "A1_1") (pintype "passive"))
      (node (ref "R325") (pin "2") (pinfunction "2_2") (pintype "passive"))
    )
    (net (code "81") (name "/UART_4_DBG_TXD") (class "Default")
      (node (ref "IC37") (pin "2") (pinfunction "A2_2") (pintype "passive"))
      (node (ref "R323") (pin "2") (pinfunction "2_2") (pintype "passive"))
      (node (ref "R326") (pin "2") (pinfunction "2_2") (pintype "passive"))
    )
    (net (code "82") (name "/UART_4_RXD") (class "Default")
      (node (ref "R325") (pin "1") (pinfunction "1_1") (pintype "passive"))
      (node (ref "RA18") (pin "6") (pinfunction "6_6") (pintype "passive"))
    )
    (net (code "83") (name "/UART_4_TXD") (class "Default")
      (node (ref "R326") (pin "1") (pinfunction "1_1") (pintype "passive"))
      (node (ref "RA18") (pin "5") (pinfunction "5_5") (pintype "passive"))
    )
    (net (code "84") (name "/USB_DBG_CON_N") (class "Default")
      (node (ref "D48") (pin "1") (pinfunction "C_1") (pintype "power_in"))
      (node (ref "L47") (pin "1") (pinfunction "1_1") (pintype "passive"))
      (node (ref "X18") (pin "A7") (pinfunction "DN1_A7") (pintype "passive"))
      (node (ref "X18") (pin "B7") (pinfunction "DN2_B7") (pintype "passive"))
    )
    (net (code "85") (name "/USB_DBG_CON_P") (class "Default")
      (node (ref "D49") (pin "1") (pinfunction "C_1") (pintype "power_in"))
      (node (ref "L47") (pin "2") (pinfunction "2_2") (pintype "passive"))
      (node (ref "X18") (pin "A6") (pinfunction "DP1_A6") (pintype "passive"))
      (node (ref "X18") (pin "B6") (pinfunction "DP2_B6") (pintype "passive"))
    )
    (net (code "86") (name "/USB_DBG_N") (class "Default")
      (node (ref "IC33") (pin "7") (pinfunction "DM_7") (pintype "passive"))
      (node (ref "L47") (pin "4") (pinfunction "4_4") (pintype "passive"))
    )
    (net (code "87") (name "/USB_DBG_P") (class "Default")
      (node (ref "IC33") (pin "8") (pinfunction "DP_8") (pintype "passive"))
      (node (ref "L47") (pin "3") (pinfunction "3_3") (pintype "passive"))
    )
    (net (code "88") (name "GND") (class "Default")
      (node (ref "C196") (pin "1") (pinfunction "1_1") (pintype "passive"))
      (node (ref "C197") (pin "1") (pinfunction "1_1") (pintype "passive"))
      (node (ref "C198") (pin "1") (pinfunction "1_1") (pintype "passive"))
      (node (ref "C199") (pin "1") (pinfunction "1_1") (pintype "passive"))
      (node (ref "C200") (pin "1") (pinfunction "1_1") (pintype "passive"))
      (node (ref "C201") (pin "1") (pinfunction "1_1") (pintype "passive"))
      (node (ref "C202") (pin "1") (pinfunction "1_1") (pintype "passive"))
      (node (ref "C203") (pin "1") (pinfunction "1_1") (pintype "passive"))
      (node (ref "C204") (pin "1") (pinfunction "1_1") (pintype "passive"))
      (node (ref "C205") (pin "1") (pinfunction "1_1") (pintype "passive"))
      (node (ref "C206") (pin "1") (pinfunction "1_1") (pintype "passive"))
      (node (ref "C207") (pin "1") (pinfunction "1_1") (pintype "passive"))
      (node (ref "C208") (pin "1") (pinfunction "1_1") (pintype "passive"))
      (node (ref "C209") (pin "1") (pinfunction "1_1") (pintype "passive"))
      (node (ref "C210") (pin "1") (pinfunction "1_1") (pintype "passive"))
      (node (ref "C212") (pin "1") (pinfunction "1_1") (pintype "passive"))
      (node (ref "C213") (pin "1") (pinfunction "1_1") (pintype "passive"))
      (node (ref "C214") (pin "1") (pinfunction "1_1") (pintype "passive"))
      (node (ref "C215") (pin "1") (pinfunction "1_1") (pintype "passive"))
      (node (ref "C216") (pin "2") (pinfunction "2_2") (pintype "passive"))
      (node (ref "C218") (pin "1") (pinfunction "1_1") (pintype "passive"))
      (node (ref "C219") (pin "1") (pinfunction "1_1") (pintype "passive"))
      (node (ref "C220") (pin "1") (pinfunction "1_1") (pintype "passive"))
      (node (ref "C221") (pin "1") (pinfunction "1_1") (pintype "passive"))
      (node (ref "C222") (pin "1") (pinfunction "1_1") (pintype "passive"))
      (node (ref "C223") (pin "1") (pinfunction "1_1") (pintype "passive"))
      (node (ref "D48") (pin "2") (pinfunction "A_2") (pintype "power_in"))
      (node (ref "D49") (pin "2") (pinfunction "A_2") (pintype "power_in"))
      (node (ref "D51") (pin "A") (pinfunction "A_A") (pintype "passive"))
      (node (ref "D52") (pin "A") (pinfunction "A_A") (pintype "passive"))
      (node (ref "IC33") (pin "1") (pinfunction "GND_1") (pintype "passive"))
      (node (ref "IC33") (pin "10") (pinfunction "AGND_10") (pintype "passive"))
      (node (ref "IC33") (pin "11") (pinfunction "GND_11") (pintype "passive"))
      (node (ref "IC33") (pin "13") (pinfunction "TEST_13") (pintype "passive"))
      (node (ref "IC33") (pin "15") (pinfunction "GND_15") (pintype "passive"))
      (node (ref "IC33") (pin "25") (pinfunction "GND_25") (pintype "passive"))
      (node (ref "IC33") (pin "35") (pinfunction "GND_35") (pintype "passive"))
      (node (ref "IC33") (pin "47") (pinfunction "GND_47") (pintype "passive"))
      (node (ref "IC33") (pin "5") (pinfunction "GND_5") (pintype "passive"))
      (node (ref "IC33") (pin "51") (pinfunction "GND_51") (pintype "passive"))
      (node (ref "IC34") (pin "15") (pinfunction "DIR1_15") (pintype "passive"))
      (node (ref "IC34") (pin "16") (pinfunction "DIR2_16") (pintype "passive"))
      (node (ref "IC34") (pin "6") (pinfunction "DIR4_6") (pintype "passive"))
      (node (ref "IC34") (pin "8") (pinfunction "GND_8") (pintype "power_in"))
      (node (ref "IC35") (pin "5") (pinfunction "VSS_5") (pintype "passive"))
      (node (ref "IC36") (pin "8") (pinfunction "GND_8") (pintype "power_in"))
      (node (ref "IC37") (pin "15") (pinfunction "DIR1_15") (pintype "passive"))
      (node (ref "IC37") (pin "5") (pinfunction "DIR3_5") (pintype "passive"))
      (node (ref "IC37") (pin "8") (pinfunction "GND_8") (pintype "power_in"))
      (node (ref "IC38") (pin "2") (pinfunction "GND_2") (pintype "passive"))
      (node (ref "LED23") (pin "K") (pinfunction "K_K") (pintype "passive"))
      (node (ref "LED24") (pin "K") (pinfunction "K_K") (pintype "passive"))
      (node (ref "LED25") (pin "K") (pinfunction "K_K") (pintype "passive"))
      (node (ref "LED26") (pin "K") (pinfunction "K_K") (pintype "passive"))
      (node (ref "LED27") (pin "K") (pinfunction "K_K") (pintype "passive"))
      (node (ref "LED28") (pin "K") (pinfunction "K_K") (pintype "passive"))
      (node (ref "OSC2") (pin "2") (pinfunction "OSC2_2") (pintype "passive"))
      (node (ref "OSC2") (pin "4") (pinfunction "OSC3_4") (pintype "passive"))
      (node (ref "R297") (pin "1") (pinfunction "1_1") (pintype "passive"))
      (node (ref "R298") (pin "1") (pinfunction "1_1") (pintype "passive"))
      (node (ref "R306") (pin "1") (pinfunction "1_1") (pintype "passive"))
      (node (ref "R311") (pin "1") (pinfunction "1_1") (pintype "passive"))
      (node (ref "R330") (pin "1") (pinfunction "1_1") (pintype "passive"))
      (node (ref "T37") (pin "1") (pinfunction "S_1") (pintype "passive"))
      (node (ref "T37") (pin "4") (pinfunction "S_4") (pintype "passive"))
      (node (ref "X18") (pin "A1") (pinfunction "GND_A1") (pintype "passive"))
      (node (ref "X18") (pin "A12") (pinfunction "GND_A12") (pintype "passive"))
      (node (ref "X18") (pin "B1") (pinfunction "GND_B1") (pintype "passive"))
      (node (ref "X18") (pin "B12") (pinfunction "GND_B12") (pintype "passive"))
    )
    (net (code "89") (name "GND_CHASSIS") (class "Default")
      (node (ref "X18") (pin "SH1") (pinfunction "SHIELD_SH1") (pintype "passive"))
      (node (ref "X18") (pin "SH2") (pinfunction "SHIELD_SH2") (pintype "passive"))
      (node (ref "X18") (pin "SH3") (pinfunction "SHIELD_SH3") (pintype "passive"))
      (node (ref "X18") (pin "SH4") (pinfunction "SHIELD_SH4") (pintype "passive"))
    )
    (net (code "90") (name "JTAG_1_VREF") (class "Default")
      (node (ref "C214") (pin "2") (pinfunction "2_2") (pintype "passive"))
      (node (ref "C217") (pin "2") (pinfunction "2_2") (pintype "passive"))
      (node (ref "IC34") (pin "14") (pinfunction "VCCA_14") (pintype "power_in"))
      (node (ref "IC34") (pin "5") (pinfunction "DIR3_5") (pintype "passive"))
      (node (ref "JP6") (pin "1") (pinfunction "1_1") (pintype "passive"))
      (node (ref "R300") (pin "2") (pinfunction "2_2") (pintype "passive"))
    )
    (net (code "91") (name "Net-(C196-Pad2)") (class "Default")
      (node (ref "C196") (pin "2") (pinfunction "2_2") (pintype "passive"))
      (node (ref "L43") (pin "2") (pinfunction "2_2") (pintype "passive"))
      (node (ref "X18") (pin "A4") (pinfunction "VBUS_A4") (pintype "passive"))
      (node (ref "X18") (pin "A9") (pinfunction "VBUS_A9") (pintype "passive"))
      (node (ref "X18") (pin "B4") (pinfunction "VBUS_B4") (pintype "passive"))
      (node (ref "X18") (pin "B9") (pinfunction "VBUS_B9") (pintype "passive"))
    )
    (net (code "92") (name "Net-(IC33-BDBUS7)") (class "Default")
      (node (ref "IC33") (pin "34") (pinfunction "BDBUS7_34") (pintype "passive"))
      (node (ref "R303") (pin "2") (pinfunction "2_2") (pintype "passive"))
    )
    (net (code "93") (name "Net-(IC33-OSCI)") (class "Default")
      (node (ref "C216") (pin "1") (pinfunction "1_1") (pintype "passive"))
      (node (ref "IC33") (pin "2") (pinfunction "OSCI_2") (pintype "passive"))
      (node (ref "OSC2") (pin "3") (pinfunction "OSC2_3") (pintype "passive"))
      (node (ref "R314") (pin "2") (pinfunction "2_2") (pintype "passive"))
    )
    (net (code "94") (name "Net-(IC33-OSCO)") (class "Default")
      (node (ref "IC33") (pin "3") (pinfunction "OSCO_3") (pintype "passive"))
      (node (ref "R316") (pin "1") (pinfunction "1_1") (pintype "passive"))
    )
    (net (code "95") (name "Net-(IC33-REF)") (class "Default")
      (node (ref "IC33") (pin "6") (pinfunction "REF_6") (pintype "passive"))
      (node (ref "R306") (pin "2") (pinfunction "2_2") (pintype "passive"))
    )
    (net (code "96") (name "Net-(IC33-VPHY)") (class "Default")
      (node (ref "C199") (pin "2") (pinfunction "2_2") (pintype "passive"))
      (node (ref "C200") (pin "2") (pinfunction "2_2") (pintype "passive"))
      (node (ref "IC33") (pin "4") (pinfunction "VPHY_4") (pintype "passive"))
      (node (ref "L45") (pin "2") (pinfunction "2_2") (pintype "passive"))
    )
    (net (code "97") (name "Net-(IC33-VPLL)") (class "Default")
      (node (ref "C197") (pin "2") (pinfunction "2_2") (pintype "passive"))
      (node (ref "C198") (pin "2") (pinfunction "2_2") (pintype "passive"))
      (node (ref "IC33") (pin "9") (pinfunction "VPLL_9") (pintype "passive"))
      (node (ref "L44") (pin "2") (pinfunction "2_2") (pintype "passive"))
    )
    (net (code "98") (name "Net-(IC33-~{RESET})") (class "Default")
      (node (ref "C210") (pin "2") (pinfunction "2_2") (pintype "passive"))
      (node (ref "D50") (pin "A") (pinfunction "A_A") (pintype "passive"))
      (node (ref "IC33") (pin "14") (pinfunction "~{RESET}_14") (pintype "passive"))
      (node (ref "R302") (pin "1") (pinfunction "1_1") (pintype "passive"))
    )
    (net (code "99") (name "Net-(IC34-~{OE})") (class "Default")
      (node (ref "C217") (pin "1") (pinfunction "1_1") (pintype "passive"))
      (node (ref "D51") (pin "C") (pinfunction "C_C") (pintype "passive"))
      (node (ref "IC34") (pin "7") (pinfunction "~{OE}_7") (pintype "passive"))
      (node (ref "JP6") (pin "2") (pinfunction "2_2") (pintype "passive"))
      (node (ref "R311") (pin "2") (pinfunction "2_2") (pintype "passive"))
    )
    (net (code "100") (name "Net-(IC35-DO)") (class "Default")
      (node (ref "IC35") (pin "4") (pinfunction "DO_4") (pintype "passive"))
      (node (ref "R307") (pin "1") (pinfunction "1_1") (pintype "passive"))
      (node (ref "R310") (pin "1") (pinfunction "1_1") (pintype "passive"))
    )
    (net (code "101") (name "Net-(IC37-~{OE})") (class "Default")
      (node (ref "C224") (pin "1") (pinfunction "1_1") (pintype "passive"))
      (node (ref "D52") (pin "C") (pinfunction "C_C") (pintype "passive"))
      (node (ref "IC37") (pin "7") (pinfunction "~{OE}_7") (pintype "passive"))
      (node (ref "R330") (pin "2") (pinfunction "2_2") (pintype "passive"))
    )
    (net (code "102") (name "Net-(LED23-PadA)") (class "Default")
      (node (ref "LED23") (pin "A") (pinfunction "A_A") (pintype "passive"))
      (node (ref "R303") (pin "1") (pinfunction "1_1") (pintype "passive"))
    )
    (net (code "103") (name "Net-(LED24-PadA)") (class "Default")
      (node (ref "LED24") (pin "A") (pinfunction "A_A") (pintype "passive"))
      (node (ref "R315") (pin "1") (pinfunction "1_1") (pintype "passive"))
    )
    (net (code "104") (name "Net-(LED25-PadA)") (class "Default")
      (node (ref "LED25") (pin "A") (pinfunction "A_A") (pintype "passive"))
      (node (ref "R317") (pin "1") (pinfunction "1_1") (pintype "passive"))
    )
    (net (code "105") (name "Net-(LED26-PadA)") (class "Default")
      (node (ref "LED26") (pin "A") (pinfunction "A_A") (pintype "passive"))
      (node (ref "R319") (pin "1") (pinfunction "1_1") (pintype "passive"))
    )
    (net (code "106") (name "Net-(LED27-PadA)") (class "Default")
      (node (ref "LED27") (pin "A") (pinfunction "A_A") (pintype "passive"))
      (node (ref "R320") (pin "1") (pinfunction "1_1") (pintype "passive"))
    )
    (net (code "107") (name "Net-(LED28-PadA)") (class "Default")
      (node (ref "LED28") (pin "A") (pinfunction "A_A") (pintype "passive"))
      (node (ref "R331") (pin "1") (pinfunction "1_1") (pintype "passive"))
    )
    (net (code "108") (name "Net-(OSC2A-OSC1)") (class "Default")
      (node (ref "C218") (pin "2") (pinfunction "2_2") (pintype "passive"))
      (node (ref "OSC2") (pin "1") (pinfunction "OSC1_1") (pintype "passive"))
      (node (ref "R314") (pin "1") (pinfunction "1_1") (pintype "passive"))
      (node (ref "R316") (pin "2") (pinfunction "2_2") (pintype "passive"))
    )
    (net (code "109") (name "Net-(T37A-D)") (class "Default")
      (node (ref "R245") (pin "1") (pinfunction "1_1") (pintype "passive"))
      (node (ref "T37") (pin "5") (pinfunction "G_5") (pintype "passive"))
      (node (ref "T37") (pin "6") (pinfunction "D_6") (pintype "passive"))
    )
    (net (code "110") (name "Net-(X18A-CC1)") (class "Default")
      (node (ref "R298") (pin "2") (pinfunction "2_2") (pintype "passive"))
      (node (ref "X18") (pin "A5") (pinfunction "CC1_A5") (pintype "passive"))
    )
    (net (code "111") (name "Net-(X18A-CC2)") (class "Default")
      (node (ref "R297") (pin "2") (pinfunction "2_2") (pintype "passive"))
      (node (ref "X18") (pin "B5") (pinfunction "CC2_B5") (pintype "passive"))
    )
    (net (code "112") (name "unconnected-(IC33-ADBUS0-Pad16)") (class "Default")
      (node (ref "IC33") (pin "16") (pinfunction "ADBUS0_16") (pintype "passive+no_connect"))
    )
    (net (code "113") (name "unconnected-(IC33-ADBUS1-Pad17)") (class "Default")
      (node (ref "IC33") (pin "17") (pinfunction "ADBUS1_17") (pintype "passive+no_connect"))
    )
    (net (code "114") (name "unconnected-(IC33-ADBUS2-Pad18)") (class "Default")
      (node (ref "IC33") (pin "18") (pinfunction "ADBUS2_18") (pintype "passive+no_connect"))
    )
    (net (code "115") (name "unconnected-(IC33-ADBUS3-Pad19)") (class "Default")
      (node (ref "IC33") (pin "19") (pinfunction "ADBUS3_19") (pintype "passive+no_connect"))
    )
    (net (code "116") (name "unconnected-(IC33-BDBUS5-Pad32)") (class "Default")
      (node (ref "IC33") (pin "32") (pinfunction "BDBUS5_32") (pintype "passive+no_connect"))
    )
    (net (code "117") (name "unconnected-(IC33-BDBUS6-Pad33)") (class "Default")
      (node (ref "IC33") (pin "33") (pinfunction "BDBUS6_33") (pintype "passive+no_connect"))
    )
    (net (code "118") (name "unconnected-(IC33-CDBUS2-Pad40)") (class "Default")
      (node (ref "IC33") (pin "40") (pinfunction "CDBUS2_40") (pintype "passive+no_connect"))
    )
    (net (code "119") (name "unconnected-(IC33-CDBUS3-Pad41)") (class "Default")
      (node (ref "IC33") (pin "41") (pinfunction "CDBUS3_41") (pintype "passive+no_connect"))
    )
    (net (code "120") (name "unconnected-(IC33-CDBUS4-Pad43)") (class "Default")
      (node (ref "IC33") (pin "43") (pinfunction "CDBUS4_43") (pintype "passive+no_connect"))
    )
    (net (code "121") (name "unconnected-(IC33-CDBUS5-Pad44)") (class "Default")
      (node (ref "IC33") (pin "44") (pinfunction "CDBUS5_44") (pintype "passive+no_connect"))
    )
    (net (code "122") (name "unconnected-(IC33-CDBUS6-Pad45)") (class "Default")
      (node (ref "IC33") (pin "45") (pinfunction "CDBUS6_45") (pintype "passive+no_connect"))
    )
    (net (code "123") (name "unconnected-(IC33-CDBUS7-Pad46)") (class "Default")
      (node (ref "IC33") (pin "46") (pinfunction "CDBUS7_46") (pintype "passive+no_connect"))
    )
    (net (code "124") (name "unconnected-(IC33-DDBUS2-Pad53)") (class "Default")
      (node (ref "IC33") (pin "53") (pinfunction "DDBUS2_53") (pintype "passive+no_connect"))
    )
    (net (code "125") (name "unconnected-(IC33-DDBUS3-Pad54)") (class "Default")
      (node (ref "IC33") (pin "54") (pinfunction "DDBUS3_54") (pintype "passive+no_connect"))
    )
    (net (code "126") (name "unconnected-(IC33-DDBUS4-Pad55)") (class "Default")
      (node (ref "IC33") (pin "55") (pinfunction "DDBUS4_55") (pintype "passive+no_connect"))
    )
    (net (code "127") (name "unconnected-(IC33-DDBUS5-Pad57)") (class "Default")
      (node (ref "IC33") (pin "57") (pinfunction "DDBUS5_57") (pintype "passive+no_connect"))
    )
    (net (code "128") (name "unconnected-(IC33-DDBUS6-Pad58)") (class "Default")
      (node (ref "IC33") (pin "58") (pinfunction "DDBUS6_58") (pintype "passive+no_connect"))
    )
    (net (code "129") (name "unconnected-(IC33-DDBUS7-Pad59)") (class "Default")
      (node (ref "IC33") (pin "59") (pinfunction "DDBUS7_59") (pintype "passive+no_connect"))
    )
    (net (code "130") (name "unconnected-(IC33-~{SUSPEND}-Pad36)") (class "Default")
      (node (ref "IC33") (pin "36") (pinfunction "~{SUSPEND}_36") (pintype "passive+no_connect"))
    )
    (net (code "131") (name "unconnected-(IC35-NC-Pad7)") (class "Default")
      (node (ref "IC35") (pin "7") (pinfunction "NC_7") (pintype "passive+no_connect"))
    )
    (net (code "132") (name "unconnected-(IC35-ORG-Pad6)") (class "Default")
      (node (ref "IC35") (pin "6") (pinfunction "ORG_6") (pintype "passive+no_connect"))
    )
    (net (code "133") (name "unconnected-(IC36-QA-Pad15)") (class "Default")
      (node (ref "IC36") (pin "15") (pinfunction "QA_15") (pintype "output+no_connect"))
    )
    (net (code "134") (name "unconnected-(IC36-QB-Pad1)") (class "Default")
      (node (ref "IC36") (pin "1") (pinfunction "QB_1") (pintype "output+no_connect"))
    )
    (net (code "135") (name "unconnected-(IC36-QC-Pad2)") (class "Default")
      (node (ref "IC36") (pin "2") (pinfunction "QC_2") (pintype "output+no_connect"))
    )
    (net (code "136") (name "unconnected-(IC36-QD-Pad3)") (class "Default")
      (node (ref "IC36") (pin "3") (pinfunction "QD_3") (pintype "output+no_connect"))
    )
    (net (code "137") (name "unconnected-(IC36-QH'-Pad9)") (class "Default")
      (node (ref "IC36") (pin "9") (pinfunction "QH'_9") (pintype "output+no_connect"))
    )
    (net (code "138") (name "unconnected-(IC38-N{slash}C-Pad4)") (class "Default")
      (node (ref "IC38") (pin "4") (pinfunction "N/C_4") (pintype "passive+no_connect"))
    )
    (net (code "139") (name "unconnected-(X18A-SBU1-PadA8)") (class "Default")
      (node (ref "X18") (pin "A8") (pinfunction "SBU1_A8") (pintype "passive+no_connect"))
    )
    (net (code "140") (name "unconnected-(X18A-SBU2-PadB8)") (class "Default")
      (node (ref "X18") (pin "B8") (pinfunction "SBU2_B8") (pintype "passive+no_connect"))
    )
    (net (code "141") (name "unconnected-(X18A-SSRXN1-PadB10)") (class "Default")
      (node (ref "X18") (pin "B10") (pinfunction "SSRXN1_B10") (pintype "passive+no_connect"))
    )
    (net (code "142") (name "unconnected-(X18A-SSRXN2-PadA10)") (class "Default")
      (node (ref "X18") (pin "A10") (pinfunction "SSRXN2_A10") (pintype "passive+no_connect"))
    )
    (net (code "143") (name "unconnected-(X18A-SSRXP1-PadB11)") (class "Default")
      (node (ref "X18") (pin "B11") (pinfunction "SSRXP1_B11") (pintype "passive+no_connect"))
    )
    (net (code "144") (name "unconnected-(X18A-SSRXP2-PadA11)") (class "Default")
      (node (ref "X18") (pin "A11") (pinfunction "SSRXP2_A11") (pintype "passive+no_connect"))
    )
    (net (code "145") (name "unconnected-(X18A-SSTXN1-PadA3)") (class "Default")
      (node (ref "X18") (pin "A3") (pinfunction "SSTXN1_A3") (pintype "passive+no_connect"))
    )
    (net (code "146") (name "unconnected-(X18A-SSTXN2-PadB3)") (class "Default")
      (node (ref "X18") (pin "B3") (pinfunction "SSTXN2_B3") (pintype "passive+no_connect"))
    )
    (net (code "147") (name "unconnected-(X18A-SSTXP1-PadA2)") (class "Default")
      (node (ref "X18") (pin "A2") (pinfunction "SSTXP1_A2") (pintype "passive+no_connect"))
    )
    (net (code "148") (name "unconnected-(X18A-SSTXP2-PadB2)") (class "Default")
      (node (ref "X18") (pin "B2") (pinfunction "SSTXP2_B2") (pintype "passive+no_connect"))
    )
  )
)
